# EDFA_Connector.net
KiCad netlist of a schematic drawn in Altium Designer
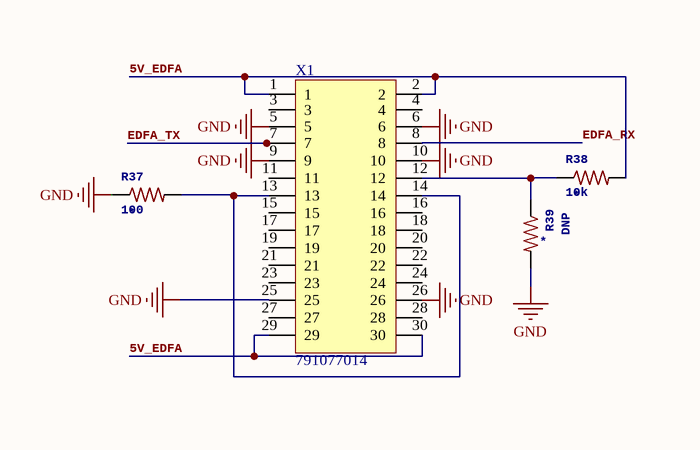
[diagram p0: EDFA Connector.SchDoc]

(export (version "E")
  (design (tool "Eeschema 10.0.6"))
  (components
    (comp (ref "R37")
      (value "100")
      (footprint "0603R")
      (description "RESISTOR, American symbol")
      (fields (field (name "NAME") "*"))
      (libsource (lib "rcl") (part "R-US_R0603"))
    )
    (comp (ref "R38")
      (value "10k")
      (footprint "0603R")
      (description "RESISTOR, American symbol")
      (fields (field (name "NAME") "*"))
      (libsource (lib "rcl") (part "R-US_R0603"))
    )
    (comp (ref "R39")
      (value "DNP")
      (footprint "0603R")
      (description "RESISTOR, American symbol")
      (fields (field (name "NAME") "*"))
      (libsource (lib "rcl") (part "R-US_R0603"))
    )
    (comp (ref "X1")
      (value "791077014")
      (footprint "791077014")
      (libsource (lib "DaughterBoard") (part "791077014"))
    )
  )
  (nets
    (net (code "1") (name "/5V_EDFA") (class "Default")
      (node (ref "R38") (pin "2") (pinfunction "2_2") (pintype "passive"))
      (node (ref "X1") (pin "1") (pinfunction "1_1") (pintype "passive"))
      (node (ref "X1") (pin "2") (pinfunction "2_2") (pintype "passive"))
      (node (ref "X1") (pin "29") (pinfunction "29_29") (pintype "passive"))
      (node (ref "X1") (pin "30") (pinfunction "30_30") (pintype "passive"))
    )
    (net (code "2") (name "/EDFA_RX") (class "Default")
      (node (ref "X1") (pin "8") (pinfunction "8_8") (pintype "passive"))
    )
    (net (code "3") (name "/EDFA_TX") (class "Default")
      (node (ref "X1") (pin "7") (pinfunction "7_7") (pintype "passive"))
    )
    (net (code "4") (name "GND") (class "Default")
      (node (ref "R37") (pin "1") (pinfunction "1_1") (pintype "passive"))
      (node (ref "R39") (pin "2") (pinfunction "2_2") (pintype "passive"))
      (node (ref "X1") (pin "10") (pinfunction "10_10") (pintype "passive"))
      (node (ref "X1") (pin "25") (pinfunction "25_25") (pintype "passive"))
      (node (ref "X1") (pin "26") (pinfunction "26_26") (pintype "passive"))
      (node (ref "X1") (pin "5") (pinfunction "5_5") (pintype "passive"))
      (node (ref "X1") (pin "6") (pinfunction "6_6") (pintype "passive"))
      (node (ref "X1") (pin "9") (pinfunction "9_9") (pintype "passive"))
    )
    (net (code "5") (name "Net-(R37-Pad2)") (class "Default")
      (node (ref "R37") (pin "2") (pinfunction "2_2") (pintype "passive"))
      (node (ref "X1") (pin "13") (pinfunction "13_13") (pintype "passive"))
      (node (ref "X1") (pin "14") (pinfunction "14_14") (pintype "passive"))
    )
    (net (code "6") (name "Net-(R38-Pad1)") (class "Default")
      (node (ref "R38") (pin "1") (pinfunction "1_1") (pintype "passive"))
      (node (ref "R39") (pin "1") (pinfunction "1_1") (pintype "passive"))
      (node (ref "X1") (pin "12") (pinfunction "12_12") (pintype "passive"))
    )
    (net (code "7") (name "unconnected-(X1-Pad3)") (class "Default")
      (node (ref "X1") (pin "3") (pinfunction "3_3") (pintype "passive"))
    )
    (net (code "8") (name "unconnected-(X1-Pad4)") (class "Default")
      (node (ref "X1") (pin "4") (pinfunction "4_4") (pintype "passive"))
    )
    (net (code "9") (name "unconnected-(X1-Pad11)") (class "Default")
      (node (ref "X1") (pin "11") (pinfunction "11_11") (pintype "passive"))
    )
    (net (code "10") (name "unconnected-(X1-Pad15)") (class "Default")
      (node (ref "X1") (pin "15") (pinfunction "15_15") (pintype "passive"))
    )
    (net (code "11") (name "unconnected-(X1-Pad16)") (class "Default")
      (node (ref "X1") (pin "16") (pinfunction "16_16") (pintype "passive"))
    )
    (net (code "12") (name "unconnected-(X1-Pad17)") (class "Default")
      (node (ref "X1") (pin "17") (pinfunction "17_17") (pintype "passive"))
    )
    (net (code "13") (name "unconnected-(X1-Pad18)") (class "Default")
      (node (ref "X1") (pin "18") (pinfunction "18_18") (pintype "passive"))
    )
    (net (code "14") (name "unconnected-(X1-Pad19)") (class "Default")
      (node (ref "X1") (pin "19") (pinfunction "19_19") (pintype "passive"))
    )
    (net (code "15") (name "unconnected-(X1-Pad20)") (class "Default")
      (node (ref "X1") (pin "20") (pinfunction "20_20") (pintype "passive"))
    )
    (net (code "16") (name "unconnected-(X1-Pad21)") (class "Default")
      (node (ref "X1") (pin "21") (pinfunction "21_21") (pintype "passive"))
    )
    (net (code "17") (name "unconnected-(X1-Pad22)") (class "Default")
      (node (ref "X1") (pin "22") (pinfunction "22_22") (pintype "passive"))
    )
    (net (code "18") (name "unconnected-(X1-Pad23)") (class "Default")
      (node (ref "X1") (pin "23") (pinfunction "23_23") (pintype "passive"))
    )
    (net (code "19") (name "unconnected-(X1-Pad24)") (class "Default")
      (node (ref "X1") (pin "24") (pinfunction "24_24") (pintype "passive"))
    )
    (net (code "20") (name "unconnected-(X1-Pad27)") (class "Default")
      (node (ref "X1") (pin "27") (pinfunction "27_27") (pintype "passive"))
    )
    (net (code "21") (name "unconnected-(X1-Pad28)") (class "Default")
      (node (ref "X1") (pin "28") (pinfunction "28_28") (pintype "passive"))
    )
  )
)
